# MB1296-Connectors.net
KiCad netlist of a schematic drawn in Altium Designer
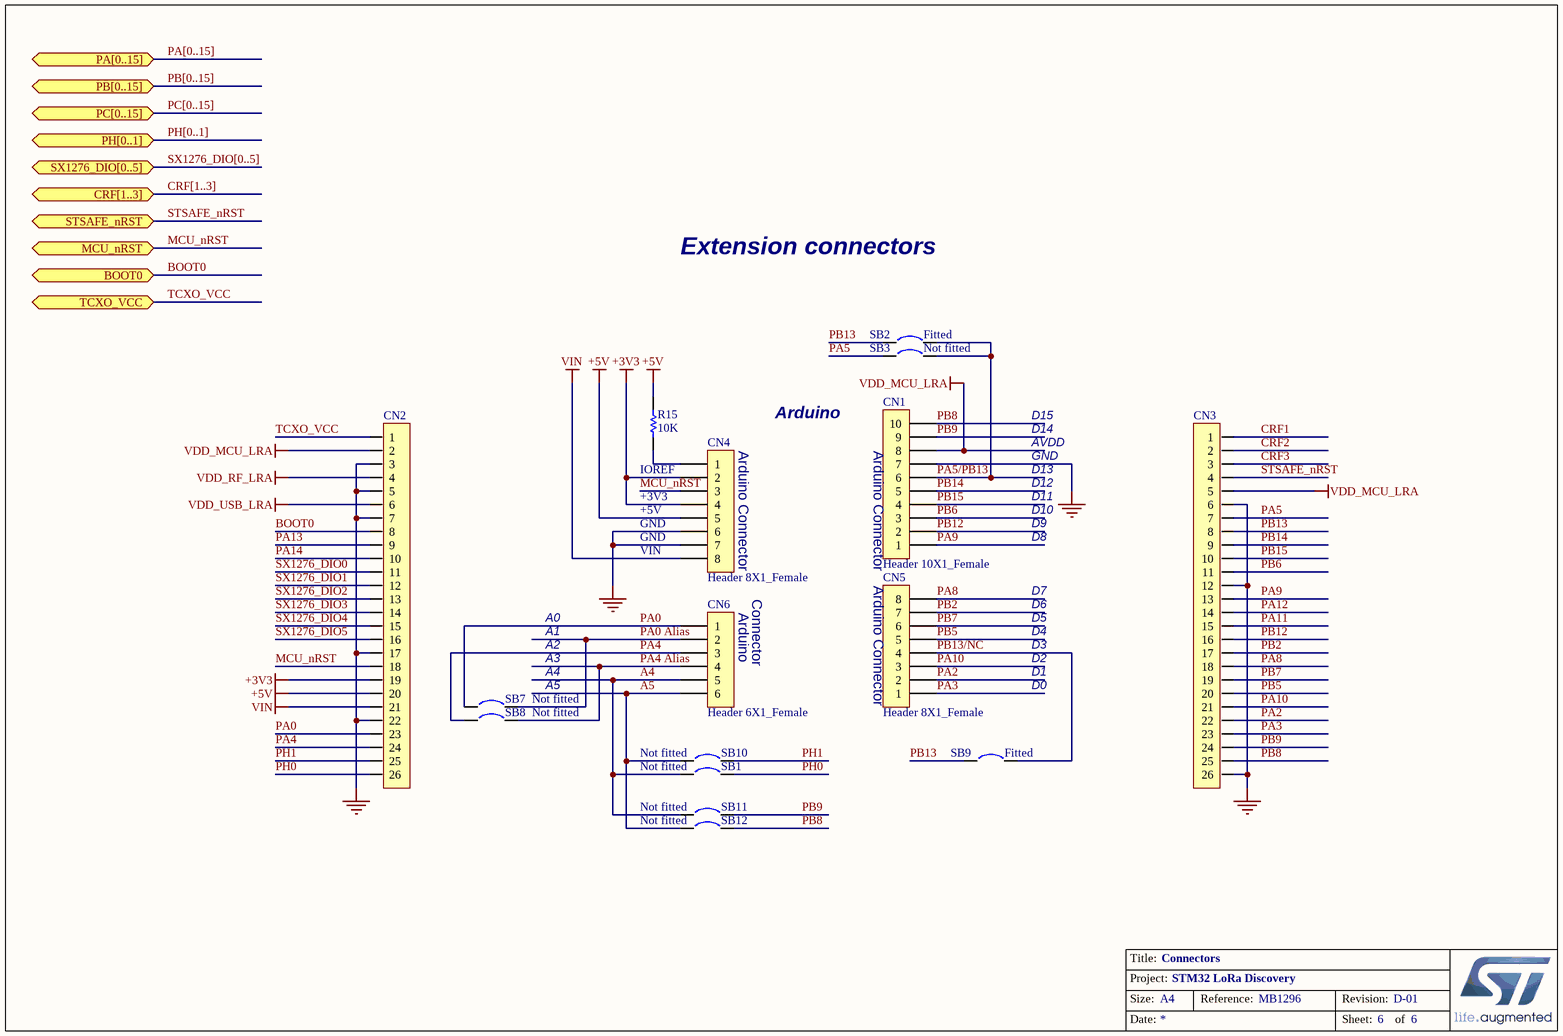
[diagram p0: MB1296-Connectors.SchDoc]

(export (version "E")
  (design (tool "Eeschema 10.0.6"))
  (components
    (comp (ref "CN1")
      (value "Header 10X1_Female")
      (footprint "Header 1x10 Female (Wrapping)")
      (description "Header, 10-Pin, Single row,female")
      (fields (field (name "MANUFACTURER") "Lyconn") (field (name "PROVIDED BY") "Subcon"))
      (libsource (lib "MCD16-033-STM32_LRA_Eval_Board_1") (part "Header 10X1_Female"))
    )
    (comp (ref "CN2")
      (value "~")
      (footprint "HEADER 1X26 (2.54) Male")
      (description "Connector header 26x1 2.54mm female")
      (fields (field (name "MANUFACTURER") "Samtec"))
      (libsource (lib "Connector") (part "CON_SLW-126-01-T-S"))
    )
    (comp (ref "CN3")
      (value "~")
      (footprint "HEADER 1X26 (2.54) Male")
      (description "Connector header 26x1 2.54mm female")
      (fields (field (name "MANUFACTURER") "Samtec"))
      (libsource (lib "") (part "CON_SLW-126-01-T-S_1"))
    )
    (comp (ref "CN4")
      (value "Header 8X1_Female")
      (footprint "Header 1x8Female (Wrapping)")
      (description "Header, 8-Pin, Single row,female")
      (fields (field (name "MANUFACTURER") "Lyconn") (field (name "PROVIDED BY") "Subcon"))
      (libsource (lib "") (part "Header 8X1_Female_1"))
    )
    (comp (ref "CN5")
      (value "Header 8X1_Female")
      (footprint "Header 1x8Female (Wrapping)")
      (description "Header, 8-Pin, Single row,female")
      (fields (field (name "MANUFACTURER") "Lyconn") (field (name "PROVIDED BY") "Subcon"))
      (libsource (lib "MCD16-033-STM32_LRA_Eval_Board_1") (part "Header 8X1_Female"))
    )
    (comp (ref "CN6")
      (value "Header 6X1_Female")
      (footprint "Header 1x6 Female (Wrapping)")
      (description "Header, 6-Pin, Single row,female")
      (fields (field (name "MANUFACTURER") "Lyconn") (field (name "PROVIDED BY") "Subcon"))
      (libsource (lib "MCD16-033-STM32_LRA_Eval_Board_1") (part "Header 6X1_Female"))
    )
    (comp (ref "R15")
      (value "10K")
      (footprint "0603R")
      (description "Resistor 0603")
      (fields (field (name "MANUFACTURER") "YAGEO") (field (name "PROVIDED BY") "Subcon"))
      (libsource (lib "MCD16-033-STM32_LRA_Eval_Board_1") (part "Resistor_ST"))
    )
    (comp (ref "SB1")
      (value "Circuit Breaker")
      (footprint "JP2_SMD")
      (libsource (lib "MCD16-033-STM32_LRA_Eval_Board_1") (part "Circuit Breaker"))
    )
    (comp (ref "SB2")
      (value "Circuit Breaker")
      (footprint "JP2_SMD")
      (libsource (lib "MCD16-033-STM32_LRA_Eval_Board_1") (part "Circuit Breaker"))
    )
    (comp (ref "SB3")
      (value "Circuit Breaker")
      (footprint "JP2_SMD")
      (libsource (lib "MCD16-033-STM32_LRA_Eval_Board_1") (part "Circuit Breaker"))
    )
    (comp (ref "SB7")
      (value "Circuit Breaker")
      (footprint "JP2_SMD")
      (libsource (lib "MCD16-033-STM32_LRA_Eval_Board_1") (part "Circuit Breaker"))
    )
    (comp (ref "SB8")
      (value "Circuit Breaker")
      (footprint "JP2_SMD")
      (libsource (lib "MCD16-033-STM32_LRA_Eval_Board_1") (part "Circuit Breaker"))
    )
    (comp (ref "SB9")
      (value "Circuit Breaker")
      (footprint "JP2_SMD")
      (libsource (lib "MCD16-033-STM32_LRA_Eval_Board_1") (part "Circuit Breaker"))
    )
    (comp (ref "SB10")
      (value "Circuit Breaker")
      (footprint "JP2_SMD")
      (libsource (lib "MCD16-033-STM32_LRA_Eval_Board_1") (part "Circuit Breaker"))
    )
    (comp (ref "SB11")
      (value "Circuit Breaker")
      (footprint "JP2_SMD")
      (libsource (lib "MCD16-033-STM32_LRA_Eval_Board_1") (part "Circuit Breaker"))
    )
    (comp (ref "SB12")
      (value "Circuit Breaker")
      (footprint "JP2_SMD")
      (libsource (lib "MCD16-033-STM32_LRA_Eval_Board_1") (part "Circuit Breaker"))
    )
  )
  (nets
    (net (code "27") (name "+3V3") (class "Default")
      (node (ref "CN2") (pin "19") (pinfunction "19_19") (pintype "passive"))
      (node (ref "CN4") (pin "2") (pinfunction "2_2") (pintype "passive"))
      (node (ref "CN4") (pin "4") (pinfunction "4_4") (pintype "passive"))
    )
    (net (code "28") (name "+5V") (class "Default")
      (node (ref "CN2") (pin "20") (pinfunction "20_20") (pintype "passive"))
      (node (ref "CN4") (pin "5") (pinfunction "5_5") (pintype "passive"))
      (node (ref "R15") (pin "1") (pinfunction "1_1") (pintype "passive"))
    )
    (net (code "29") (name "/A4") (class "Default")
      (node (ref "CN6") (pin "5") (pinfunction "5_5") (pintype "passive"))
      (node (ref "SB1") (pin "1") (pinfunction "1_1") (pintype "passive"))
      (node (ref "SB11") (pin "1") (pinfunction "1_1") (pintype "passive"))
    )
    (net (code "30") (name "/A5") (class "Default")
      (node (ref "CN6") (pin "6") (pinfunction "6_6") (pintype "passive"))
      (node (ref "SB10") (pin "1") (pinfunction "1_1") (pintype "passive"))
      (node (ref "SB12") (pin "1") (pinfunction "1_1") (pintype "passive"))
    )
    (net (code "31") (name "/BOOT0") (class "Default")
      (node (ref "CN2") (pin "8") (pinfunction "8_8") (pintype "passive"))
    )
    (net (code "32") (name "/CRF1") (class "Default")
      (node (ref "CN3") (pin "1") (pinfunction "1_1") (pintype "passive"))
    )
    (net (code "33") (name "/CRF2") (class "Default")
      (node (ref "CN3") (pin "2") (pinfunction "2_2") (pintype "passive"))
    )
    (net (code "34") (name "/CRF3") (class "Default")
      (node (ref "CN3") (pin "3") (pinfunction "3_3") (pintype "passive"))
    )
    (net (code "36") (name "/MCU_nRST") (class "Default")
      (node (ref "CN2") (pin "18") (pinfunction "18_18") (pintype "passive"))
      (node (ref "CN4") (pin "3") (pinfunction "3_3") (pintype "passive"))
    )
    (net (code "37") (name "/PA0") (class "Default")
      (node (ref "CN2") (pin "23") (pinfunction "23_23") (pintype "passive"))
      (node (ref "CN6") (pin "1") (pinfunction "1_1") (pintype "passive"))
      (node (ref "SB7") (pin "1") (pinfunction "1_1") (pintype "passive"))
    )
    (net (code "38") (name "/PA0 Alias") (class "Default")
      (node (ref "CN6") (pin "2") (pinfunction "2_2") (pintype "passive"))
      (node (ref "SB7") (pin "2") (pinfunction "2_2") (pintype "passive"))
    )
    (net (code "39") (name "/PA2") (class "Default")
      (node (ref "CN3") (pin "22") (pinfunction "22_22") (pintype "passive"))
      (node (ref "CN5") (pin "2") (pinfunction "2_2") (pintype "passive"))
    )
    (net (code "40") (name "/PA3") (class "Default")
      (node (ref "CN3") (pin "23") (pinfunction "23_23") (pintype "passive"))
      (node (ref "CN5") (pin "1") (pinfunction "1_1") (pintype "passive"))
    )
    (net (code "41") (name "/PA4") (class "Default")
      (node (ref "CN2") (pin "24") (pinfunction "24_24") (pintype "passive"))
      (node (ref "CN6") (pin "3") (pinfunction "3_3") (pintype "passive"))
      (node (ref "SB8") (pin "1") (pinfunction "1_1") (pintype "passive"))
    )
    (net (code "42") (name "/PA4 Alias") (class "Default")
      (node (ref "CN6") (pin "4") (pinfunction "4_4") (pintype "passive"))
      (node (ref "SB8") (pin "2") (pinfunction "2_2") (pintype "passive"))
    )
    (net (code "43") (name "/PA5") (class "Default")
      (node (ref "CN3") (pin "7") (pinfunction "7_7") (pintype "passive"))
      (node (ref "SB3") (pin "1") (pinfunction "1_1") (pintype "passive"))
    )
    (net (code "44") (name "/PA5{slash}PB13") (class "Default")
      (node (ref "CN1") (pin "6") (pinfunction "6_6") (pintype "passive"))
      (node (ref "SB2") (pin "2") (pinfunction "2_2") (pintype "passive"))
      (node (ref "SB3") (pin "2") (pinfunction "2_2") (pintype "passive"))
    )
    (net (code "45") (name "/PA8") (class "Default")
      (node (ref "CN3") (pin "18") (pinfunction "18_18") (pintype "passive"))
      (node (ref "CN5") (pin "8") (pinfunction "8_8") (pintype "passive"))
    )
    (net (code "46") (name "/PA9") (class "Default")
      (node (ref "CN1") (pin "1") (pinfunction "1_1") (pintype "passive"))
      (node (ref "CN3") (pin "13") (pinfunction "13_13") (pintype "passive"))
    )
    (net (code "47") (name "/PA10") (class "Default")
      (node (ref "CN3") (pin "21") (pinfunction "21_21") (pintype "passive"))
      (node (ref "CN5") (pin "3") (pinfunction "3_3") (pintype "passive"))
    )
    (net (code "48") (name "/PA11") (class "Default")
      (node (ref "CN3") (pin "15") (pinfunction "15_15") (pintype "passive"))
    )
    (net (code "49") (name "/PA12") (class "Default")
      (node (ref "CN3") (pin "14") (pinfunction "14_14") (pintype "passive"))
    )
    (net (code "50") (name "/PA13") (class "Default")
      (node (ref "CN2") (pin "9") (pinfunction "9_9") (pintype "passive"))
    )
    (net (code "51") (name "/PA14") (class "Default")
      (node (ref "CN2") (pin "10") (pinfunction "10_10") (pintype "passive"))
    )
    (net (code "53") (name "/PB2") (class "Default")
      (node (ref "CN3") (pin "17") (pinfunction "17_17") (pintype "passive"))
      (node (ref "CN5") (pin "7") (pinfunction "7_7") (pintype "passive"))
    )
    (net (code "54") (name "/PB5") (class "Default")
      (node (ref "CN3") (pin "20") (pinfunction "20_20") (pintype "passive"))
      (node (ref "CN5") (pin "5") (pinfunction "5_5") (pintype "passive"))
    )
    (net (code "55") (name "/PB6") (class "Default")
      (node (ref "CN1") (pin "3") (pinfunction "3_3") (pintype "passive"))
      (node (ref "CN3") (pin "11") (pinfunction "11_11") (pintype "passive"))
    )
    (net (code "56") (name "/PB7") (class "Default")
      (node (ref "CN3") (pin "19") (pinfunction "19_19") (pintype "passive"))
      (node (ref "CN5") (pin "6") (pinfunction "6_6") (pintype "passive"))
    )
    (net (code "57") (name "/PB8") (class "Default")
      (node (ref "CN1") (pin "10") (pinfunction "10_10") (pintype "passive"))
      (node (ref "CN3") (pin "25") (pinfunction "25_25") (pintype "passive"))
      (node (ref "SB12") (pin "2") (pinfunction "2_2") (pintype "passive"))
    )
    (net (code "58") (name "/PB9") (class "Default")
      (node (ref "CN1") (pin "9") (pinfunction "9_9") (pintype "passive"))
      (node (ref "CN3") (pin "24") (pinfunction "24_24") (pintype "passive"))
      (node (ref "SB11") (pin "2") (pinfunction "2_2") (pintype "passive"))
    )
    (net (code "59") (name "/PB12") (class "Default")
      (node (ref "CN1") (pin "2") (pinfunction "2_2") (pintype "passive"))
      (node (ref "CN3") (pin "16") (pinfunction "16_16") (pintype "passive"))
    )
    (net (code "60") (name "/PB13") (class "Default")
      (node (ref "CN3") (pin "8") (pinfunction "8_8") (pintype "passive"))
      (node (ref "SB2") (pin "1") (pinfunction "1_1") (pintype "passive"))
      (node (ref "SB9") (pin "1") (pinfunction "1_1") (pintype "passive"))
    )
    (net (code "61") (name "/PB13{slash}NC") (class "Default")
      (node (ref "CN5") (pin "4") (pinfunction "4_4") (pintype "passive"))
      (node (ref "SB9") (pin "2") (pinfunction "2_2") (pintype "passive"))
    )
    (net (code "62") (name "/PB14") (class "Default")
      (node (ref "CN1") (pin "5") (pinfunction "5_5") (pintype "passive"))
      (node (ref "CN3") (pin "9") (pinfunction "9_9") (pintype "passive"))
    )
    (net (code "63") (name "/PB15") (class "Default")
      (node (ref "CN1") (pin "4") (pinfunction "4_4") (pintype "passive"))
      (node (ref "CN3") (pin "10") (pinfunction "10_10") (pintype "passive"))
    )
    (net (code "66") (name "/PH0") (class "Default")
      (node (ref "CN2") (pin "26") (pinfunction "26_26") (pintype "passive"))
      (node (ref "SB1") (pin "2") (pinfunction "2_2") (pintype "passive"))
    )
    (net (code "67") (name "/PH1") (class "Default")
      (node (ref "CN2") (pin "25") (pinfunction "25_25") (pintype "passive"))
      (node (ref "SB10") (pin "2") (pinfunction "2_2") (pintype "passive"))
    )
    (net (code "69") (name "/STSAFE_nRST") (class "Default")
      (node (ref "CN3") (pin "4") (pinfunction "4_4") (pintype "passive"))
    )
    (net (code "70") (name "/SX1276_DIO0") (class "Default")
      (node (ref "CN2") (pin "11") (pinfunction "11_11") (pintype "passive"))
    )
    (net (code "71") (name "/SX1276_DIO1") (class "Default")
      (node (ref "CN2") (pin "12") (pinfunction "12_12") (pintype "passive"))
    )
    (net (code "72") (name "/SX1276_DIO2") (class "Default")
      (node (ref "CN2") (pin "13") (pinfunction "13_13") (pintype "passive"))
    )
    (net (code "73") (name "/SX1276_DIO3") (class "Default")
      (node (ref "CN2") (pin "14") (pinfunction "14_14") (pintype "passive"))
    )
    (net (code "74") (name "/SX1276_DIO4") (class "Default")
      (node (ref "CN2") (pin "15") (pinfunction "15_15") (pintype "passive"))
    )
    (net (code "75") (name "/SX1276_DIO5") (class "Default")
      (node (ref "CN2") (pin "16") (pinfunction "16_16") (pintype "passive"))
    )
    (net (code "77") (name "/TCXO_VCC") (class "Default")
      (node (ref "CN2") (pin "1") (pinfunction "1_1") (pintype "passive"))
    )
    (net (code "78") (name "GND") (class "Default")
      (node (ref "CN1") (pin "7") (pinfunction "7_7") (pintype "passive"))
      (node (ref "CN2") (pin "17") (pinfunction "17_17") (pintype "passive"))
      (node (ref "CN2") (pin "22") (pinfunction "22_22") (pintype "passive"))
      (node (ref "CN2") (pin "3") (pinfunction "3_3") (pintype "passive"))
      (node (ref "CN2") (pin "5") (pinfunction "5_5") (pintype "passive"))
      (node (ref "CN2") (pin "7") (pinfunction "7_7") (pintype "passive"))
      (node (ref "CN3") (pin "12") (pinfunction "12_12") (pintype "passive"))
      (node (ref "CN3") (pin "26") (pinfunction "26_26") (pintype "passive"))
      (node (ref "CN3") (pin "6") (pinfunction "6_6") (pintype "passive"))
      (node (ref "CN4") (pin "6") (pinfunction "6_6") (pintype "passive"))
      (node (ref "CN4") (pin "7") (pinfunction "7_7") (pintype "passive"))
    )
    (net (code "79") (name "Net-(CN4-Pad1)") (class "Default")
      (node (ref "CN4") (pin "1") (pinfunction "1_1") (pintype "passive"))
      (node (ref "R15") (pin "2") (pinfunction "2_2") (pintype "passive"))
    )
    (net (code "80") (name "VDD_MCU_LRA") (class "Default")
      (node (ref "CN1") (pin "8") (pinfunction "8_8") (pintype "passive"))
      (node (ref "CN2") (pin "2") (pinfunction "2_2") (pintype "passive"))
      (node (ref "CN3") (pin "5") (pinfunction "5_5") (pintype "passive"))
    )
    (net (code "81") (name "VDD_RF_LRA") (class "Default")
      (node (ref "CN2") (pin "4") (pinfunction "4_4") (pintype "passive"))
    )
    (net (code "82") (name "VDD_USB_LRA") (class "Default")
      (node (ref "CN2") (pin "6") (pinfunction "6_6") (pintype "passive"))
    )
    (net (code "83") (name "VIN") (class "Default")
      (node (ref "CN2") (pin "21") (pinfunction "21_21") (pintype "passive"))
      (node (ref "CN4") (pin "8") (pinfunction "8_8") (pintype "passive"))
    )
  )
)
